# Adafruit_2_7in_Tri-Color_eInk_Display.net
KiCad netlist of a schematic drawn in EAGLE
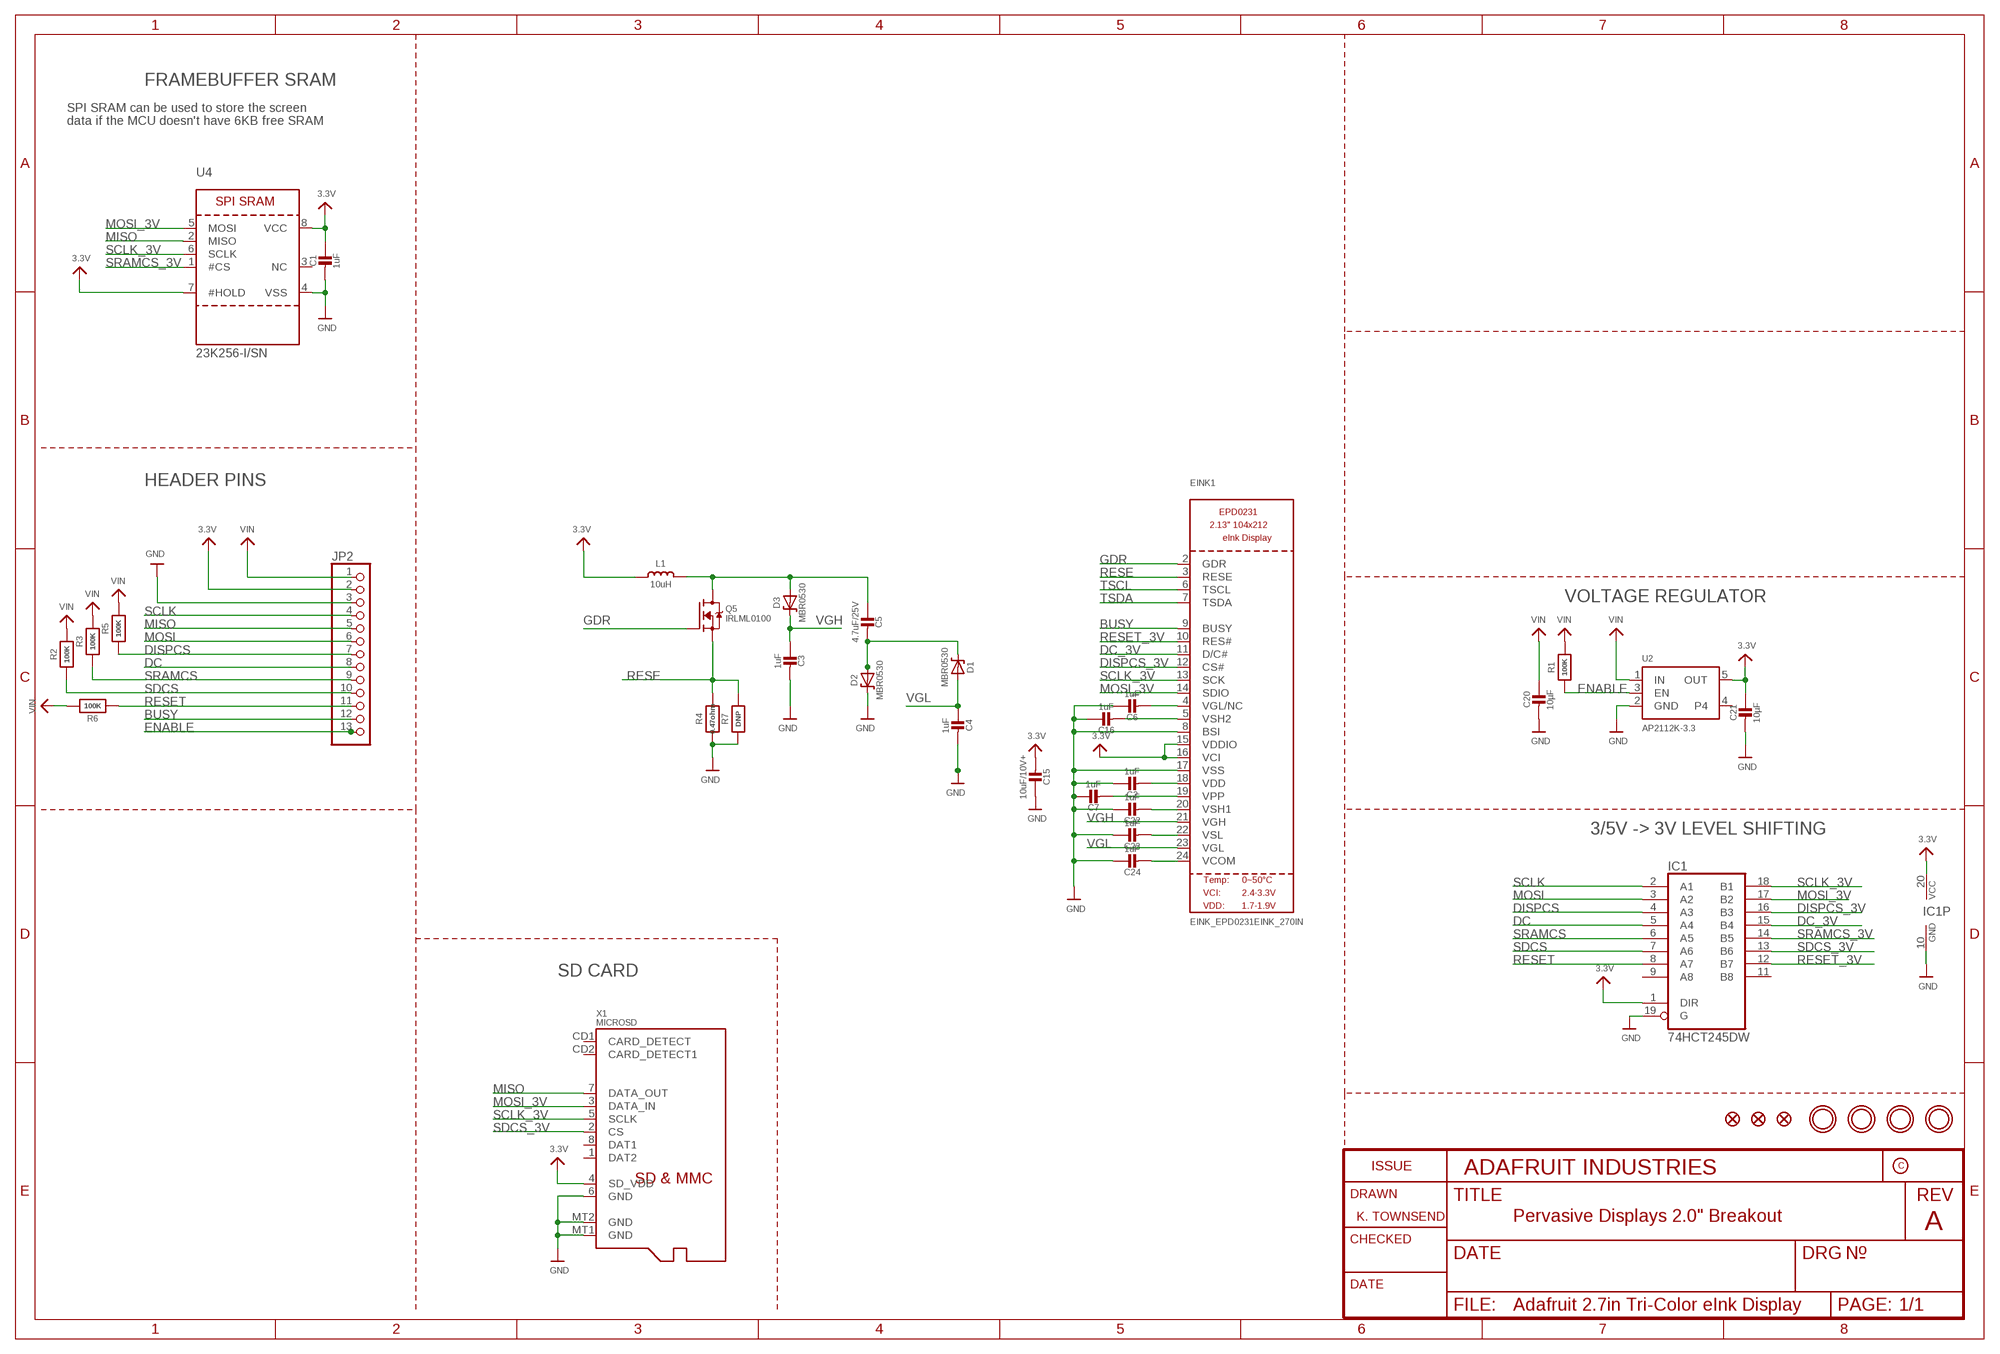
[diagram p0: schematic, sheet 1]

(export (version "E")
  (design (tool "Eeschema 10.0.6"))
  (components
    (comp (ref "C1")
      (value "1uF")
      (footprint "eagle-import:0805_10MGAP")
      (libsource (lib "eagle-import") (part "CAP_CERAMIC0805_10MGAP"))
    )
    (comp (ref "C2")
      (value "1uF")
      (footprint "eagle-import:0805-NO")
      (libsource (lib "eagle-import") (part "CAP_CERAMIC0805-NOOUTLINE"))
    )
    (comp (ref "C3")
      (value "1uF")
      (footprint "eagle-import:0805-NO")
      (libsource (lib "eagle-import") (part "CAP_CERAMIC0805-NOOUTLINE"))
    )
    (comp (ref "C4")
      (value "1uF")
      (footprint "eagle-import:0805-NO")
      (libsource (lib "eagle-import") (part "CAP_CERAMIC0805-NOOUTLINE"))
    )
    (comp (ref "C5")
      (value "4.7uF/25V")
      (footprint "eagle-import:0805-NO")
      (libsource (lib "eagle-import") (part "CAP_CERAMIC0805-NOOUTLINE"))
    )
    (comp (ref "C6")
      (value "1uF")
      (footprint "eagle-import:0805-NO")
      (libsource (lib "eagle-import") (part "CAP_CERAMIC0805-NOOUTLINE"))
    )
    (comp (ref "C7")
      (value "1uF")
      (footprint "eagle-import:0805-NO")
      (libsource (lib "eagle-import") (part "CAP_CERAMIC0805-NOOUTLINE"))
    )
    (comp (ref "C15")
      (value "10uF/10V+")
      (footprint "eagle-import:0805-NO")
      (libsource (lib "eagle-import") (part "CAP_CERAMIC0805-NOOUTLINE"))
    )
    (comp (ref "C16")
      (value "1uF")
      (footprint "eagle-import:0805-NO")
      (libsource (lib "eagle-import") (part "CAP_CERAMIC0805-NOOUTLINE"))
    )
    (comp (ref "C20")
      (value "10µF")
      (footprint "eagle-import:0805-NO")
      (libsource (lib "eagle-import") (part "CAP_CERAMIC0805-NOOUTLINE"))
    )
    (comp (ref "C21")
      (value "10µF")
      (footprint "eagle-import:0805-NO")
      (libsource (lib "eagle-import") (part "CAP_CERAMIC0805-NOOUTLINE"))
    )
    (comp (ref "C22")
      (value "1uF")
      (footprint "eagle-import:0805-NO")
      (libsource (lib "eagle-import") (part "CAP_CERAMIC0805-NOOUTLINE"))
    )
    (comp (ref "C23")
      (value "1uF")
      (footprint "eagle-import:0805-NO")
      (libsource (lib "eagle-import") (part "CAP_CERAMIC0805-NOOUTLINE"))
    )
    (comp (ref "C24")
      (value "1uF")
      (footprint "eagle-import:0805-NO")
      (libsource (lib "eagle-import") (part "CAP_CERAMIC0805-NOOUTLINE"))
    )
    (comp (ref "D1")
      (value "MBR0530")
      (footprint "eagle-import:SOD-123")
      (libsource (lib "eagle-import") (part "DIODE-SCHOTTKYSOD-123"))
    )
    (comp (ref "D2")
      (value "MBR0530")
      (footprint "eagle-import:SOD-123")
      (libsource (lib "eagle-import") (part "DIODE-SCHOTTKYSOD-123"))
    )
    (comp (ref "D3")
      (value "MBR0530")
      (footprint "eagle-import:SOD-123")
      (libsource (lib "eagle-import") (part "DIODE-SCHOTTKYSOD-123"))
    )
    (comp (ref "EINK1")
      (value "EINK_EPD0231EINK_270IN")
      (footprint "eagle-import:EINK_270IN")
      (libsource (lib "eagle-import") (part "EINK_EPD0231EINK_270IN"))
    )
    (comp (ref "FID1")
      (value "FIDUCIAL_1MM")
      (footprint "eagle-import:FIDUCIAL_1MM")
      (libsource (lib "eagle-import") (part "FIDUCIAL_1MM"))
    )
    (comp (ref "FID2")
      (value "FIDUCIAL_1MM")
      (footprint "eagle-import:FIDUCIAL_1MM")
      (libsource (lib "eagle-import") (part "FIDUCIAL_1MM"))
    )
    (comp (ref "FID3")
      (value "FIDUCIAL_1MM")
      (footprint "eagle-import:FIDUCIAL_1MM")
      (libsource (lib "eagle-import") (part "FIDUCIAL_1MM"))
    )
    (comp (ref "IC1")
      (value "74HCT245DW")
      (footprint "eagle-import:SO20W")
      (libsource (lib "eagle-import") (part "74245DWHCT"))
    )
    (comp (ref "JP2")
      (value "HEADER-1X13")
      (footprint "eagle-import:1X13_ROUND_70")
      (libsource (lib "eagle-import") (part "HEADER-1X13"))
    )
    (comp (ref "L1")
      (value "10uH")
      (footprint "eagle-import:INDUCTOR_4X4MM_NR401")
      (libsource (lib "eagle-import") (part "INDUCTORNR401"))
    )
    (comp (ref "Q5")
      (value "IRLML0100")
      (footprint "eagle-import:SOT23-3")
      (libsource (lib "eagle-import") (part "IRLML2060TRPBF"))
    )
    (comp (ref "R1")
      (value "100K")
      (footprint "eagle-import:0805-NO")
      (libsource (lib "eagle-import") (part "RESISTOR0805_NOOUTLINE"))
    )
    (comp (ref "R2")
      (value "100K")
      (footprint "eagle-import:0805-NO")
      (libsource (lib "eagle-import") (part "RESISTOR0805_NOOUTLINE"))
    )
    (comp (ref "R3")
      (value "100K")
      (footprint "eagle-import:0805-NO")
      (libsource (lib "eagle-import") (part "RESISTOR0805_NOOUTLINE"))
    )
    (comp (ref "R4")
      (value "0.47ohm")
      (footprint "eagle-import:0805_10MGAP")
      (libsource (lib "eagle-import") (part "RESISTOR0805_10MGAP"))
    )
    (comp (ref "R5")
      (value "100K")
      (footprint "eagle-import:0805-NO")
      (libsource (lib "eagle-import") (part "RESISTOR0805_NOOUTLINE"))
    )
    (comp (ref "R6")
      (value "100K")
      (footprint "eagle-import:0805-NO")
      (libsource (lib "eagle-import") (part "RESISTOR0805_NOOUTLINE"))
    )
    (comp (ref "R7")
      (value "DNP")
      (footprint "eagle-import:0805_10MGAP")
      (libsource (lib "eagle-import") (part "RESISTOR0805_10MGAP"))
    )
    (comp (ref "U$3")
      (value "MOUNTINGHOLE2.5")
      (footprint "eagle-import:MOUNTINGHOLE_2.5_PLATED")
      (libsource (lib "eagle-import") (part "MOUNTINGHOLE2.5"))
    )
    (comp (ref "U$4")
      (value "MOUNTINGHOLE2.5")
      (footprint "eagle-import:MOUNTINGHOLE_2.5_PLATED")
      (libsource (lib "eagle-import") (part "MOUNTINGHOLE2.5"))
    )
    (comp (ref "U$5")
      (value "MOUNTINGHOLE2.5")
      (footprint "eagle-import:MOUNTINGHOLE_2.5_PLATED")
      (libsource (lib "eagle-import") (part "MOUNTINGHOLE2.5"))
    )
    (comp (ref "U$6")
      (value "MOUNTINGHOLE2.5")
      (footprint "eagle-import:MOUNTINGHOLE_2.5_PLATED")
      (libsource (lib "eagle-import") (part "MOUNTINGHOLE2.5"))
    )
    (comp (ref "U2")
      (value "AP2112K-3.3")
      (footprint "eagle-import:SOT23-5")
      (libsource (lib "eagle-import") (part "VREG_SOT23-5"))
    )
    (comp (ref "U4")
      (value "23K256-I/SN")
      (footprint "eagle-import:SOIC8_150MIL")
      (libsource (lib "eagle-import") (part "SRAM_SPI_SOIC8"))
    )
    (comp (ref "X1")
      (value "MICROSD")
      (footprint "eagle-import:MICROSD")
      (libsource (lib "eagle-import") (part "MICROSD"))
    )
  )
  (nets
    (net (code "1") (name "/BUSY") (class "Default")
      (node (ref "EINK1") (pin "9") (pinfunction "BUSY_9") (pintype "output"))
      (node (ref "JP2") (pin "12") (pinfunction "12_12") (pintype "passive"))
    )
    (net (code "2") (name "/DC") (class "Default")
      (node (ref "IC1") (pin "5") (pinfunction "A4_5") (pintype "bidirectional"))
      (node (ref "JP2") (pin "8") (pinfunction "8_8") (pintype "passive"))
    )
    (net (code "3") (name "/DC_3V") (class "Default")
      (node (ref "EINK1") (pin "11") (pinfunction "D/C#_11") (pintype "input"))
      (node (ref "IC1") (pin "15") (pinfunction "B4_15") (pintype "bidirectional"))
    )
    (net (code "4") (name "/DISPCS") (class "Default")
      (node (ref "IC1") (pin "4") (pinfunction "A3_4") (pintype "bidirectional"))
      (node (ref "JP2") (pin "7") (pinfunction "7_7") (pintype "passive"))
      (node (ref "R5") (pin "1") (pinfunction "1_1") (pintype "passive"))
    )
    (net (code "5") (name "/DISPCS_3V") (class "Default")
      (node (ref "EINK1") (pin "12") (pinfunction "CS#_12") (pintype "input"))
      (node (ref "IC1") (pin "16") (pinfunction "B3_16") (pintype "bidirectional"))
    )
    (net (code "6") (name "/ENABLE") (class "Default")
      (node (ref "JP2") (pin "13") (pinfunction "13_13") (pintype "passive"))
      (node (ref "R1") (pin "1") (pinfunction "1_1") (pintype "passive"))
      (node (ref "U2") (pin "3") (pinfunction "EN_3") (pintype "input"))
    )
    (net (code "7") (name "/GDR") (class "Default")
      (node (ref "EINK1") (pin "2") (pinfunction "GDR_2") (pintype "output"))
      (node (ref "Q5") (pin "1") (pinfunction "G_1") (pintype "bidirectional"))
    )
    (net (code "8") (name "/MISO") (class "Default")
      (node (ref "JP2") (pin "5") (pinfunction "5_5") (pintype "passive"))
      (node (ref "U4") (pin "2") (pinfunction "MISO_2") (pintype "output"))
      (node (ref "X1") (pin "7") (pinfunction "DATA_OUT_7") (pintype "output"))
    )
    (net (code "9") (name "/MOSI") (class "Default")
      (node (ref "IC1") (pin "3") (pinfunction "A2_3") (pintype "bidirectional"))
      (node (ref "JP2") (pin "6") (pinfunction "6_6") (pintype "passive"))
    )
    (net (code "10") (name "/MOSI_3V") (class "Default")
      (node (ref "EINK1") (pin "14") (pinfunction "SDIO_14") (pintype "bidirectional"))
      (node (ref "IC1") (pin "17") (pinfunction "B2_17") (pintype "bidirectional"))
      (node (ref "U4") (pin "5") (pinfunction "MOSI_5") (pintype "input"))
      (node (ref "X1") (pin "3") (pinfunction "DATA_IN_3") (pintype "input"))
    )
    (net (code "11") (name "/RESE") (class "Default")
      (node (ref "EINK1") (pin "3") (pinfunction "RESE_3") (pintype "input"))
      (node (ref "Q5") (pin "2") (pinfunction "S_2") (pintype "bidirectional"))
      (node (ref "R4") (pin "1") (pinfunction "1_1") (pintype "passive"))
      (node (ref "R7") (pin "1") (pinfunction "1_1") (pintype "passive"))
    )
    (net (code "12") (name "/RESET") (class "Default")
      (node (ref "IC1") (pin "8") (pinfunction "A7_8") (pintype "bidirectional"))
      (node (ref "JP2") (pin "11") (pinfunction "11_11") (pintype "passive"))
      (node (ref "R6") (pin "1") (pinfunction "1_1") (pintype "passive"))
    )
    (net (code "13") (name "/RESET_3V") (class "Default")
      (node (ref "EINK1") (pin "10") (pinfunction "RES#_10") (pintype "input"))
      (node (ref "IC1") (pin "12") (pinfunction "B7_12") (pintype "bidirectional"))
    )
    (net (code "14") (name "/SCLK") (class "Default")
      (node (ref "IC1") (pin "2") (pinfunction "A1_2") (pintype "bidirectional"))
      (node (ref "JP2") (pin "4") (pinfunction "4_4") (pintype "passive"))
    )
    (net (code "15") (name "/SCLK_3V") (class "Default")
      (node (ref "EINK1") (pin "13") (pinfunction "SCK_13") (pintype "bidirectional"))
      (node (ref "IC1") (pin "18") (pinfunction "B1_18") (pintype "bidirectional"))
      (node (ref "U4") (pin "6") (pinfunction "SCLK_6") (pintype "input"))
      (node (ref "X1") (pin "5") (pinfunction "SCLK_5") (pintype "input"))
    )
    (net (code "16") (name "/SDCS") (class "Default")
      (node (ref "IC1") (pin "7") (pinfunction "A6_7") (pintype "bidirectional"))
      (node (ref "JP2") (pin "10") (pinfunction "10_10") (pintype "passive"))
      (node (ref "R2") (pin "1") (pinfunction "1_1") (pintype "passive"))
    )
    (net (code "17") (name "/SDCS_3V") (class "Default")
      (node (ref "IC1") (pin "13") (pinfunction "B6_13") (pintype "bidirectional"))
      (node (ref "X1") (pin "2") (pinfunction "CS_2") (pintype "input"))
    )
    (net (code "18") (name "/SRAMCS") (class "Default")
      (node (ref "IC1") (pin "6") (pinfunction "A5_6") (pintype "bidirectional"))
      (node (ref "JP2") (pin "9") (pinfunction "9_9") (pintype "passive"))
      (node (ref "R3") (pin "1") (pinfunction "1_1") (pintype "passive"))
    )
    (net (code "19") (name "/SRAMCS_3V") (class "Default")
      (node (ref "IC1") (pin "14") (pinfunction "B5_14") (pintype "bidirectional"))
      (node (ref "U4") (pin "1") (pinfunction "#CS_1") (pintype "input"))
    )
    (net (code "20") (name "/TSCL") (class "Default")
      (node (ref "EINK1") (pin "6") (pinfunction "TSCL_6") (pintype "output"))
    )
    (net (code "21") (name "/TSDA") (class "Default")
      (node (ref "EINK1") (pin "7") (pinfunction "TSDA_7") (pintype "bidirectional"))
    )
    (net (code "22") (name "/VGH") (class "Default")
      (node (ref "C3") (pin "1") (pinfunction "1_1") (pintype "passive"))
      (node (ref "D3") (pin "C") (pinfunction "C_C") (pintype "passive"))
      (node (ref "EINK1") (pin "21") (pinfunction "VGH_21") (pintype "passive"))
    )
    (net (code "23") (name "/VGL") (class "Default")
      (node (ref "C4") (pin "1") (pinfunction "1_1") (pintype "passive"))
      (node (ref "D1") (pin "A") (pinfunction "A_A") (pintype "passive"))
      (node (ref "EINK1") (pin "23") (pinfunction "VGL_23") (pintype "passive"))
    )
    (net (code "24") (name "3.3V") (class "Default")
      (node (ref "C1") (pin "1") (pinfunction "1_1") (pintype "passive"))
      (node (ref "C15") (pin "2") (pinfunction "2_2") (pintype "passive"))
      (node (ref "C21") (pin "1") (pinfunction "1_1") (pintype "passive"))
      (node (ref "EINK1") (pin "15") (pinfunction "VDDIO_15") (pintype "power_in"))
      (node (ref "EINK1") (pin "16") (pinfunction "VCI_16") (pintype "power_in"))
      (node (ref "IC1") (pin "1") (pinfunction "DIR_1") (pintype "input"))
      (node (ref "IC1") (pin "20") (pinfunction "VCC_20") (pintype "power_in"))
      (node (ref "JP2") (pin "2") (pinfunction "2_2") (pintype "passive"))
      (node (ref "L1") (pin "P$2") (pinfunction "2_P$2") (pintype "passive"))
      (node (ref "U2") (pin "5") (pinfunction "OUT_5") (pintype "power_in"))
      (node (ref "U4") (pin "7") (pinfunction "#HOLD_7") (pintype "input"))
      (node (ref "U4") (pin "8") (pinfunction "VCC_8") (pintype "power_in"))
      (node (ref "X1") (pin "4") (pinfunction "SD_VDD_4") (pintype "power_in"))
    )
    (net (code "25") (name "GND") (class "Default")
      (node (ref "C1") (pin "2") (pinfunction "2_2") (pintype "passive"))
      (node (ref "C15") (pin "1") (pinfunction "1_1") (pintype "passive"))
      (node (ref "C16") (pin "1") (pinfunction "1_1") (pintype "passive"))
      (node (ref "C2") (pin "1") (pinfunction "1_1") (pintype "passive"))
      (node (ref "C20") (pin "2") (pinfunction "2_2") (pintype "passive"))
      (node (ref "C21") (pin "2") (pinfunction "2_2") (pintype "passive"))
      (node (ref "C22") (pin "1") (pinfunction "1_1") (pintype "passive"))
      (node (ref "C23") (pin "1") (pinfunction "1_1") (pintype "passive"))
      (node (ref "C24") (pin "1") (pinfunction "1_1") (pintype "passive"))
      (node (ref "C3") (pin "2") (pinfunction "2_2") (pintype "passive"))
      (node (ref "C4") (pin "2") (pinfunction "2_2") (pintype "passive"))
      (node (ref "C6") (pin "1") (pinfunction "1_1") (pintype "passive"))
      (node (ref "C7") (pin "1") (pinfunction "1_1") (pintype "passive"))
      (node (ref "D2") (pin "C") (pinfunction "C_C") (pintype "passive"))
      (node (ref "EINK1") (pin "17") (pinfunction "VSS_17") (pintype "power_in"))
      (node (ref "EINK1") (pin "8") (pinfunction "BSI_8") (pintype "input"))
      (node (ref "IC1") (pin "10") (pinfunction "GND_10") (pintype "power_in"))
      (node (ref "IC1") (pin "19") (pinfunction "G_19") (pintype "input"))
      (node (ref "JP2") (pin "3") (pinfunction "3_3") (pintype "passive"))
      (node (ref "R4") (pin "2") (pinfunction "2_2") (pintype "passive"))
      (node (ref "R7") (pin "2") (pinfunction "2_2") (pintype "passive"))
      (node (ref "U2") (pin "2") (pinfunction "GND_2") (pintype "power_in"))
      (node (ref "U4") (pin "4") (pinfunction "VSS_4") (pintype "power_in"))
      (node (ref "X1") (pin "6") (pinfunction "GND_6") (pintype "power_in"))
      (node (ref "X1") (pin "MT1") (pinfunction "GND_MT1") (pintype "power_in"))
      (node (ref "X1") (pin "MT2") (pinfunction "GND_MT2") (pintype "power_in"))
    )
    (net (code "26") (name "Net-(C5-Pad2)") (class "Default")
      (node (ref "C5") (pin "2") (pinfunction "2_2") (pintype "passive"))
      (node (ref "D1") (pin "C") (pinfunction "C_C") (pintype "passive"))
      (node (ref "D2") (pin "A") (pinfunction "A_A") (pintype "passive"))
    )
    (net (code "27") (name "Net-(EINK1-VCOM)") (class "Default")
      (node (ref "C24") (pin "2") (pinfunction "2_2") (pintype "passive"))
      (node (ref "EINK1") (pin "24") (pinfunction "VCOM_24") (pintype "passive"))
    )
    (net (code "28") (name "Net-(EINK1-VDD)") (class "Default")
      (node (ref "C2") (pin "2") (pinfunction "2_2") (pintype "passive"))
      (node (ref "EINK1") (pin "18") (pinfunction "VDD_18") (pintype "passive"))
    )
    (net (code "29") (name "Net-(EINK1-VGL{slash}NC)") (class "Default")
      (node (ref "C6") (pin "2") (pinfunction "2_2") (pintype "passive"))
      (node (ref "EINK1") (pin "4") (pinfunction "VGL/NC_4") (pintype "bidirectional"))
    )
    (net (code "30") (name "Net-(EINK1-VPP)") (class "Default")
      (node (ref "C7") (pin "2") (pinfunction "2_2") (pintype "passive"))
      (node (ref "EINK1") (pin "19") (pinfunction "VPP_19") (pintype "passive"))
    )
    (net (code "31") (name "Net-(EINK1-VSH1)") (class "Default")
      (node (ref "C22") (pin "2") (pinfunction "2_2") (pintype "passive"))
      (node (ref "EINK1") (pin "20") (pinfunction "VSH1_20") (pintype "passive"))
    )
    (net (code "32") (name "Net-(EINK1-VSH2)") (class "Default")
      (node (ref "C16") (pin "2") (pinfunction "2_2") (pintype "passive"))
      (node (ref "EINK1") (pin "5") (pinfunction "VSH2_5") (pintype "passive"))
    )
    (net (code "33") (name "Net-(EINK1-VSL)") (class "Default")
      (node (ref "C23") (pin "2") (pinfunction "2_2") (pintype "passive"))
      (node (ref "EINK1") (pin "22") (pinfunction "VSL_22") (pintype "passive"))
    )
    (net (code "34") (name "Net-(L1-1)") (class "Default")
      (node (ref "C5") (pin "1") (pinfunction "1_1") (pintype "passive"))
      (node (ref "D3") (pin "A") (pinfunction "A_A") (pintype "passive"))
      (node (ref "L1") (pin "P$1") (pinfunction "1_P$1") (pintype "passive"))
      (node (ref "Q5") (pin "3") (pinfunction "D_3") (pintype "bidirectional"))
    )
    (net (code "35") (name "VIN") (class "Default")
      (node (ref "C20") (pin "1") (pinfunction "1_1") (pintype "passive"))
      (node (ref "JP2") (pin "1") (pinfunction "1_1") (pintype "passive"))
      (node (ref "R1") (pin "2") (pinfunction "2_2") (pintype "passive"))
      (node (ref "R2") (pin "2") (pinfunction "2_2") (pintype "passive"))
      (node (ref "R3") (pin "2") (pinfunction "2_2") (pintype "passive"))
      (node (ref "R5") (pin "2") (pinfunction "2_2") (pintype "passive"))
      (node (ref "R6") (pin "2") (pinfunction "2_2") (pintype "passive"))
      (node (ref "U2") (pin "1") (pinfunction "IN_1") (pintype "power_in"))
    )
    (net (code "36") (name "unconnected-(IC1A-A8-Pad9)") (class "Default")
      (node (ref "IC1") (pin "9") (pinfunction "A8_9") (pintype "bidirectional"))
    )
    (net (code "37") (name "unconnected-(IC1A-B8-Pad11)") (class "Default")
      (node (ref "IC1") (pin "11") (pinfunction "B8_11") (pintype "bidirectional"))
    )
    (net (code "38") (name "unconnected-(U2-P4-Pad4)") (class "Default")
      (node (ref "U2") (pin "4") (pinfunction "P4_4") (pintype "bidirectional"))
    )
    (net (code "39") (name "unconnected-(U4-NC-Pad3)") (class "Default")
      (node (ref "U4") (pin "3") (pinfunction "NC_3") (pintype "no_connect"))
    )
    (net (code "40") (name "unconnected-(X1-CARD_DETECT-PadCD1)") (class "Default")
      (node (ref "X1") (pin "CD1") (pinfunction "CARD_DETECT_CD1") (pintype "passive"))
    )
    (net (code "41") (name "unconnected-(X1-CARD_DETECT1-PadCD2)") (class "Default")
      (node (ref "X1") (pin "CD2") (pinfunction "CARD_DETECT1_CD2") (pintype "passive"))
    )
    (net (code "42") (name "unconnected-(X1-DAT1-Pad8)") (class "Default")
      (node (ref "X1") (pin "8") (pinfunction "DAT1_8") (pintype "bidirectional"))
    )
    (net (code "43") (name "unconnected-(X1-DAT2-Pad1)") (class "Default")
      (node (ref "X1") (pin "1") (pinfunction "DAT2_1") (pintype "bidirectional"))
    )
  )
)
